# stm32uni.net
KiCad netlist of a schematic drawn in EAGLE
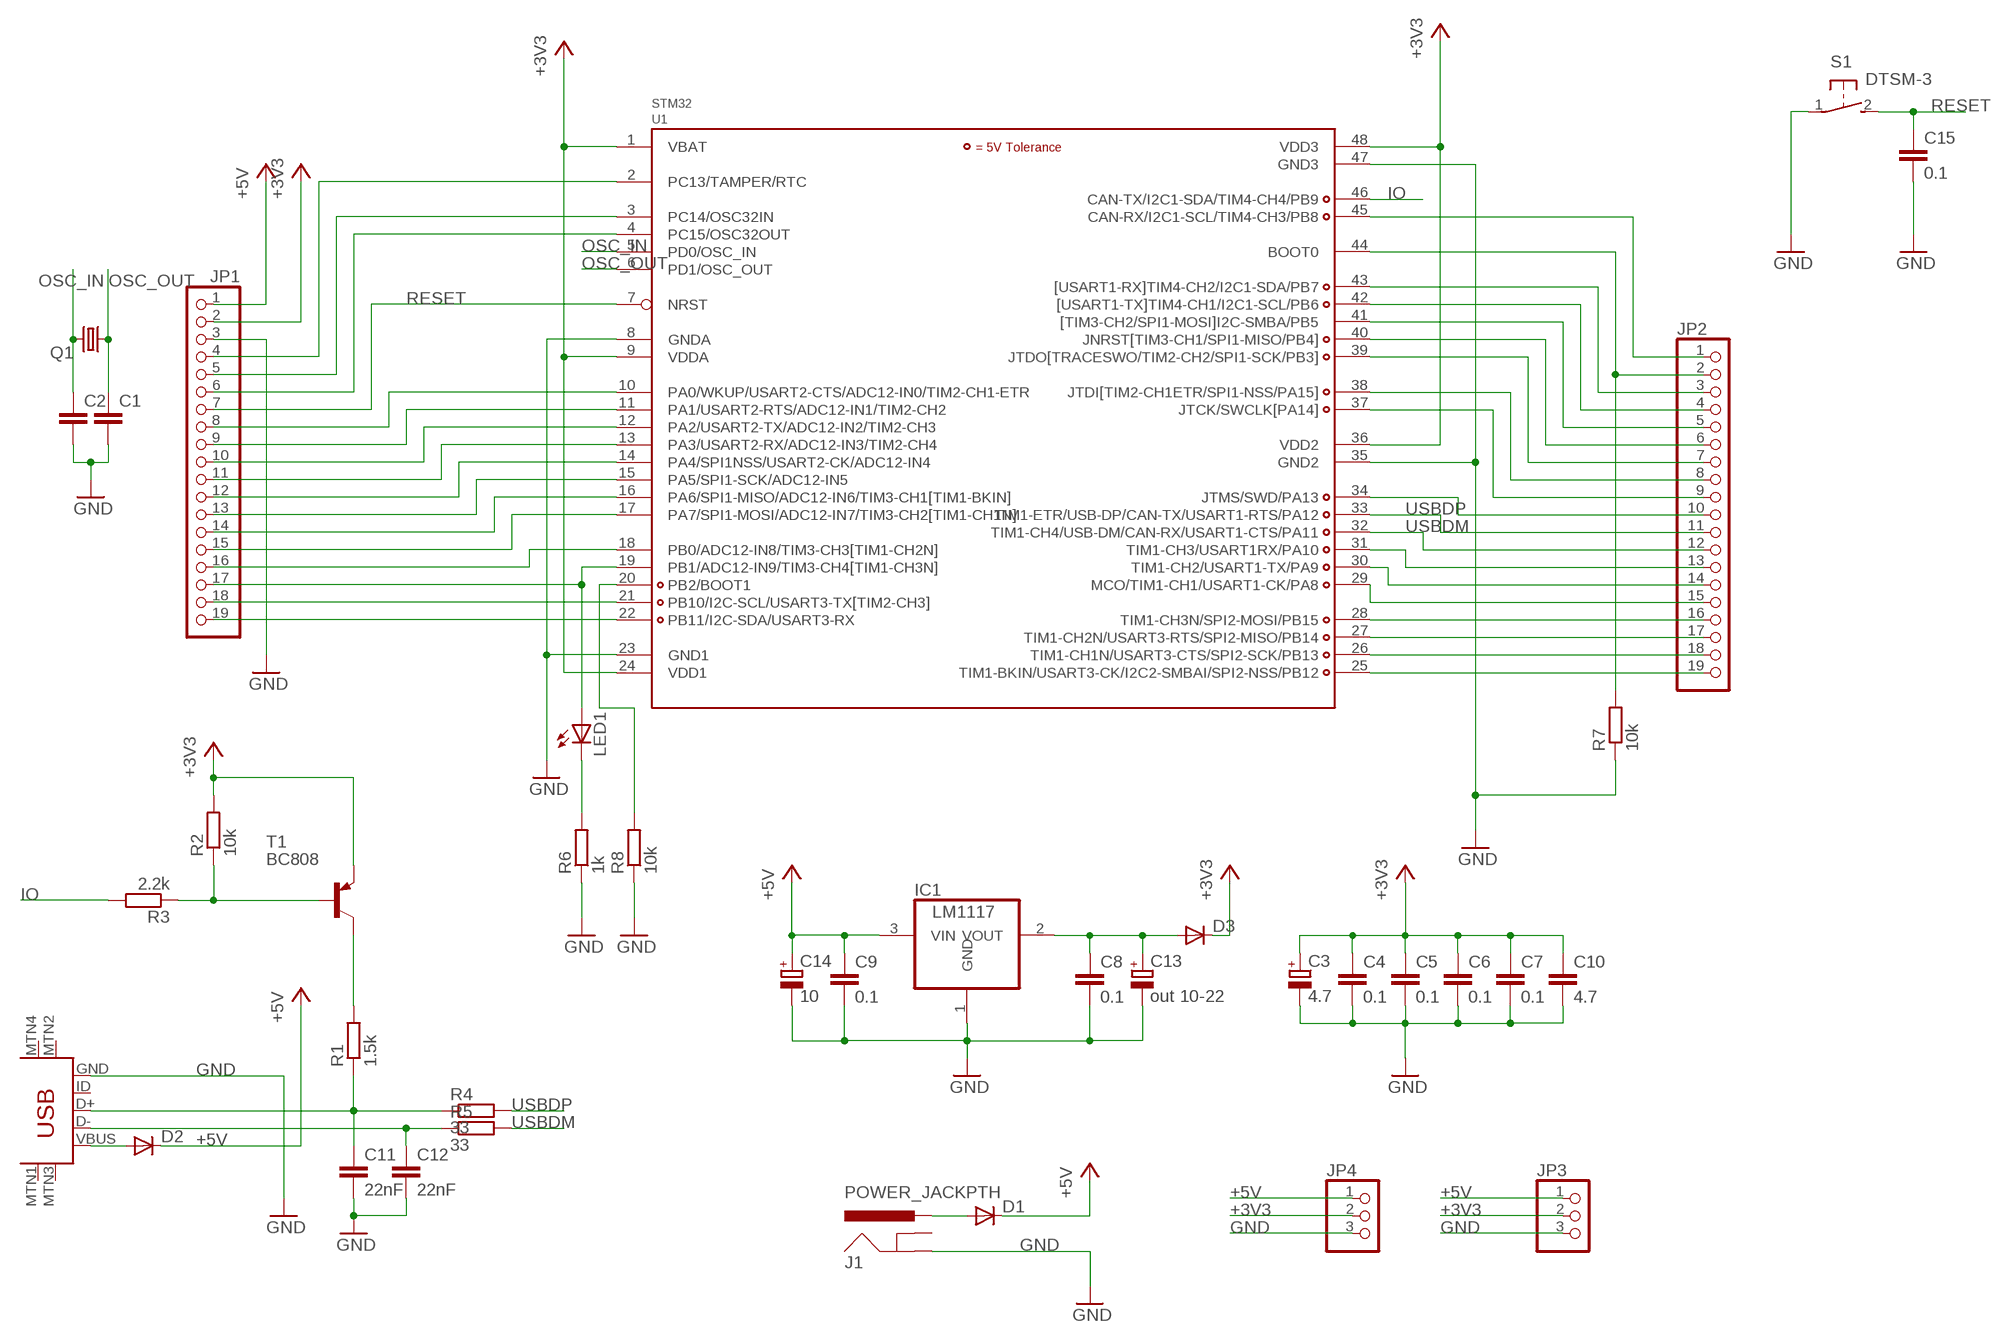
[diagram p0: schematic, sheet 1]

(export (version "E")
  (design (tool "Eeschema 10.0.6"))
  (components
    (comp (ref "C1")
      (value "C-EUC0805")
      (footprint "eagle-import:C0805")
      (libsource (lib "eagle-import") (part "C-EUC0805"))
    )
    (comp (ref "C2")
      (value "C-EUC0805")
      (footprint "eagle-import:C0805")
      (libsource (lib "eagle-import") (part "C-EUC0805"))
    )
    (comp (ref "C3")
      (value "4.7")
      (footprint "eagle-import:SMC_B")
      (libsource (lib "eagle-import") (part "CPOL-EUSMCB"))
    )
    (comp (ref "C4")
      (value "0.1")
      (footprint "eagle-import:C0805")
      (libsource (lib "eagle-import") (part "C-EUC0805"))
    )
    (comp (ref "C5")
      (value "0.1")
      (footprint "eagle-import:C0805")
      (libsource (lib "eagle-import") (part "C-EUC0805"))
    )
    (comp (ref "C6")
      (value "0.1")
      (footprint "eagle-import:C0805")
      (libsource (lib "eagle-import") (part "C-EUC0805"))
    )
    (comp (ref "C7")
      (value "0.1")
      (footprint "eagle-import:C0805")
      (libsource (lib "eagle-import") (part "C-EUC0805"))
    )
    (comp (ref "C8")
      (value "0.1")
      (footprint "eagle-import:C0805")
      (libsource (lib "eagle-import") (part "C-EUC0805"))
    )
    (comp (ref "C9")
      (value "0.1")
      (footprint "eagle-import:C0805")
      (libsource (lib "eagle-import") (part "C-EUC0805"))
    )
    (comp (ref "C10")
      (value "4.7")
      (footprint "eagle-import:C0805")
      (libsource (lib "eagle-import") (part "C-EUC0805"))
    )
    (comp (ref "C11")
      (value "22nF")
      (footprint "eagle-import:C0805")
      (libsource (lib "eagle-import") (part "C-EUC0805"))
    )
    (comp (ref "C12")
      (value "22nF")
      (footprint "eagle-import:C0805")
      (libsource (lib "eagle-import") (part "C-EUC0805"))
    )
    (comp (ref "C13")
      (value "out 10-22")
      (footprint "eagle-import:SMC_B")
      (libsource (lib "eagle-import") (part "CPOL-EUSMCB"))
    )
    (comp (ref "C14")
      (value "10")
      (footprint "eagle-import:SMC_B")
      (libsource (lib "eagle-import") (part "CPOL-EUSMCB"))
    )
    (comp (ref "C15")
      (value "0.1")
      (footprint "eagle-import:C0805")
      (libsource (lib "eagle-import") (part "C-EUC0805"))
    )
    (comp (ref "D1")
      (value "DIODE-SOD123")
      (footprint "eagle-import:SOD123")
      (libsource (lib "eagle-import") (part "DIODE-SOD123"))
    )
    (comp (ref "D2")
      (value "DIODE-SOD123")
      (footprint "eagle-import:SOD123")
      (libsource (lib "eagle-import") (part "DIODE-SOD123"))
    )
    (comp (ref "D3")
      (value "DIODE-SOD123")
      (footprint "eagle-import:SOD123")
      (libsource (lib "eagle-import") (part "DIODE-SOD123"))
    )
    (comp (ref "IC1")
      (value "LM1117")
      (footprint "eagle-import:SOT223")
      (fields (field (name "MPN") "REG1117"))
      (libsource (lib "eagle-import") (part "REG1117"))
    )
    (comp (ref "J1")
      (value "POWER_JACKPTH")
      (footprint "eagle-import:POWER_JACK_PTH")
      (libsource (lib "eagle-import") (part "POWER_JACKPTH"))
    )
    (comp (ref "JP1")
      (value "PINHD-1X19")
      (footprint "eagle-import:1X19")
      (libsource (lib "eagle-import") (part "PINHD-1X19"))
    )
    (comp (ref "JP2")
      (value "PINHD-1X19")
      (footprint "eagle-import:1X19")
      (libsource (lib "eagle-import") (part "PINHD-1X19"))
    )
    (comp (ref "JP3")
      (value "PINHD-1X3")
      (footprint "eagle-import:1X03")
      (libsource (lib "eagle-import") (part "PINHD-1X3"))
    )
    (comp (ref "JP4")
      (value "PINHD-1X3")
      (footprint "eagle-import:1X03")
      (libsource (lib "eagle-import") (part "PINHD-1X3"))
    )
    (comp (ref "LED1")
      (value "LEDCHIPLED_0805")
      (footprint "eagle-import:CHIPLED_0805")
      (libsource (lib "eagle-import") (part "LEDCHIPLED_0805"))
    )
    (comp (ref "Q1")
      (value "CRYSTALHC49UP")
      (footprint "eagle-import:HC49UP")
      (libsource (lib "eagle-import") (part "CRYSTALHC49UP"))
    )
    (comp (ref "R1")
      (value "1.5k")
      (footprint "eagle-import:R0805")
      (libsource (lib "eagle-import") (part "R-EU_R0805"))
    )
    (comp (ref "R2")
      (value "10k")
      (footprint "eagle-import:R0805")
      (libsource (lib "eagle-import") (part "R-EU_R0805"))
    )
    (comp (ref "R3")
      (value "2.2k")
      (footprint "eagle-import:R0805")
      (libsource (lib "eagle-import") (part "R-EU_R0805"))
    )
    (comp (ref "R4")
      (value "33")
      (footprint "eagle-import:R0805")
      (libsource (lib "eagle-import") (part "R-EU_R0805"))
    )
    (comp (ref "R5")
      (value "33")
      (footprint "eagle-import:R0805")
      (libsource (lib "eagle-import") (part "R-EU_R0805"))
    )
    (comp (ref "R6")
      (value "1k")
      (footprint "eagle-import:R0805")
      (libsource (lib "eagle-import") (part "R-EU_R0805"))
    )
    (comp (ref "R7")
      (value "10k")
      (footprint "eagle-import:R0805")
      (libsource (lib "eagle-import") (part "R-EU_R0805"))
    )
    (comp (ref "R8")
      (value "10k")
      (footprint "eagle-import:R0805")
      (libsource (lib "eagle-import") (part "R-EU_R0805"))
    )
    (comp (ref "S1")
      (value "DTSM-3")
      (footprint "eagle-import:DTSM-3")
      (libsource (lib "eagle-import") (part "DTSM-3"))
    )
    (comp (ref "T1")
      (value "BC808")
      (footprint "eagle-import:SOT23-BEC")
      (libsource (lib "eagle-import") (part "-PNP-SOT23-BECBC808-16"))
    )
    (comp (ref "U$1")
      (value "USB-MINIB-5PIN")
      (footprint "eagle-import:USB-MINIB")
      (libsource (lib "eagle-import") (part "USB-MINIB-5PIN"))
    )
    (comp (ref "U1")
      (value "STM32")
      (footprint "eagle-import:LQFP48")
      (libsource (lib "eagle-import") (part "STM32F103C8LQFP48"))
    )
  )
  (nets
    (net (code "1") (name "+3V3") (class "Default")
      (node (ref "C10") (pin "1") (pinfunction "1_1") (pintype "passive"))
      (node (ref "C3") (pin "+") (pinfunction "+_+") (pintype "passive"))
      (node (ref "C4") (pin "1") (pinfunction "1_1") (pintype "passive"))
      (node (ref "C5") (pin "1") (pinfunction "1_1") (pintype "passive"))
      (node (ref "C6") (pin "1") (pinfunction "1_1") (pintype "passive"))
      (node (ref "C7") (pin "1") (pinfunction "1_1") (pintype "passive"))
      (node (ref "D3") (pin "C") (pinfunction "C_C") (pintype "passive"))
      (node (ref "JP1") (pin "2") (pinfunction "2_2") (pintype "passive"))
      (node (ref "JP3") (pin "2") (pinfunction "2_2") (pintype "passive"))
      (node (ref "JP4") (pin "2") (pinfunction "2_2") (pintype "passive"))
      (node (ref "R2") (pin "2") (pinfunction "2_2") (pintype "passive"))
      (node (ref "T1") (pin "E") (pinfunction "E_E") (pintype "passive"))
      (node (ref "U1") (pin "1") (pinfunction "VBAT_1") (pintype "power_in"))
      (node (ref "U1") (pin "24") (pinfunction "VDD1_24") (pintype "power_in"))
      (node (ref "U1") (pin "36") (pinfunction "VDD2_36") (pintype "power_in"))
      (node (ref "U1") (pin "48") (pinfunction "VDD3_48") (pintype "power_in"))
      (node (ref "U1") (pin "9") (pinfunction "VDDA_9") (pintype "power_in"))
    )
    (net (code "2") (name "+5V") (class "Default")
      (node (ref "C14") (pin "+") (pinfunction "+_+") (pintype "passive"))
      (node (ref "C9") (pin "1") (pinfunction "1_1") (pintype "passive"))
      (node (ref "D1") (pin "C") (pinfunction "C_C") (pintype "passive"))
      (node (ref "D2") (pin "C") (pinfunction "C_C") (pintype "passive"))
      (node (ref "IC1") (pin "3") (pinfunction "VIN_3") (pintype "input"))
      (node (ref "JP1") (pin "1") (pinfunction "1_1") (pintype "passive"))
      (node (ref "JP3") (pin "1") (pinfunction "1_1") (pintype "passive"))
      (node (ref "JP4") (pin "1") (pinfunction "1_1") (pintype "passive"))
    )
    (net (code "3") (name "/IO") (class "Default")
      (node (ref "R3") (pin "2") (pinfunction "2_2") (pintype "passive"))
      (node (ref "U1") (pin "46") (pinfunction "CAN-TX/I2C1-SDA/TIM4-CH4/PB9_46") (pintype "bidirectional"))
    )
    (net (code "4") (name "/OSC_IN") (class "Default")
      (node (ref "C2") (pin "1") (pinfunction "1_1") (pintype "passive"))
      (node (ref "Q1") (pin "2") (pinfunction "2_2") (pintype "passive"))
      (node (ref "U1") (pin "5") (pinfunction "PD0/OSC_IN_5") (pintype "bidirectional"))
    )
    (net (code "5") (name "/OSC_OUT") (class "Default")
      (node (ref "C1") (pin "1") (pinfunction "1_1") (pintype "passive"))
      (node (ref "Q1") (pin "1") (pinfunction "1_1") (pintype "passive"))
      (node (ref "U1") (pin "6") (pinfunction "PD1/OSC_OUT_6") (pintype "bidirectional"))
    )
    (net (code "6") (name "/RESET") (class "Default")
      (node (ref "C15") (pin "1") (pinfunction "1_1") (pintype "passive"))
      (node (ref "JP1") (pin "7") (pinfunction "7_7") (pintype "passive"))
      (node (ref "S1") (pin "2") (pinfunction "2_2") (pintype "passive"))
      (node (ref "U1") (pin "7") (pinfunction "NRST_7") (pintype "bidirectional"))
    )
    (net (code "7") (name "/USBDM") (class "Default")
      (node (ref "JP2") (pin "12") (pinfunction "12_12") (pintype "passive"))
      (node (ref "R5") (pin "2") (pinfunction "2_2") (pintype "passive"))
      (node (ref "U1") (pin "32") (pinfunction "TIM1-CH4/USB-DM/CAN-RX/USART1-CTS/PA11_32") (pintype "bidirectional"))
    )
    (net (code "8") (name "/USBDP") (class "Default")
      (node (ref "JP2") (pin "11") (pinfunction "11_11") (pintype "passive"))
      (node (ref "R4") (pin "2") (pinfunction "2_2") (pintype "passive"))
      (node (ref "U1") (pin "33") (pinfunction "TIM1-ETR/USB-DP/CAN-TX/USART1-RTS/PA12_33") (pintype "bidirectional"))
    )
    (net (code "9") (name "GND") (class "Default")
      (node (ref "C1") (pin "2") (pinfunction "2_2") (pintype "passive"))
      (node (ref "C10") (pin "2") (pinfunction "2_2") (pintype "passive"))
      (node (ref "C11") (pin "2") (pinfunction "2_2") (pintype "passive"))
      (node (ref "C12") (pin "2") (pinfunction "2_2") (pintype "passive"))
      (node (ref "C13") (pin "-") (pinfunction "-_-") (pintype "passive"))
      (node (ref "C14") (pin "-") (pinfunction "-_-") (pintype "passive"))
      (node (ref "C15") (pin "2") (pinfunction "2_2") (pintype "passive"))
      (node (ref "C2") (pin "2") (pinfunction "2_2") (pintype "passive"))
      (node (ref "C3") (pin "-") (pinfunction "-_-") (pintype "passive"))
      (node (ref "C4") (pin "2") (pinfunction "2_2") (pintype "passive"))
      (node (ref "C5") (pin "2") (pinfunction "2_2") (pintype "passive"))
      (node (ref "C6") (pin "2") (pinfunction "2_2") (pintype "passive"))
      (node (ref "C7") (pin "2") (pinfunction "2_2") (pintype "passive"))
      (node (ref "C8") (pin "2") (pinfunction "2_2") (pintype "passive"))
      (node (ref "C9") (pin "2") (pinfunction "2_2") (pintype "passive"))
      (node (ref "IC1") (pin "1") (pinfunction "GND_1") (pintype "power_in"))
      (node (ref "J1") (pin "GND") (pinfunction "GND_GND") (pintype "bidirectional"))
      (node (ref "JP1") (pin "3") (pinfunction "3_3") (pintype "passive"))
      (node (ref "JP3") (pin "3") (pinfunction "3_3") (pintype "passive"))
      (node (ref "JP4") (pin "3") (pinfunction "3_3") (pintype "passive"))
      (node (ref "R6") (pin "1") (pinfunction "1_1") (pintype "passive"))
      (node (ref "R7") (pin "1") (pinfunction "1_1") (pintype "passive"))
      (node (ref "R8") (pin "1") (pinfunction "1_1") (pintype "passive"))
      (node (ref "S1") (pin "1") (pinfunction "1_1") (pintype "passive"))
      (node (ref "U$1") (pin "GND") (pinfunction "GND_GND") (pintype "bidirectional"))
      (node (ref "U1") (pin "23") (pinfunction "GND1_23") (pintype "power_in"))
      (node (ref "U1") (pin "35") (pinfunction "GND2_35") (pintype "power_in"))
      (node (ref "U1") (pin "47") (pinfunction "GND3_47") (pintype "power_in"))
      (node (ref "U1") (pin "8") (pinfunction "GNDA_8") (pintype "power_in"))
    )
    (net (code "10") (name "Net-(C11-Pad1)") (class "Default")
      (node (ref "C11") (pin "1") (pinfunction "1_1") (pintype "passive"))
      (node (ref "R1") (pin "1") (pinfunction "1_1") (pintype "passive"))
      (node (ref "R4") (pin "1") (pinfunction "1_1") (pintype "passive"))
      (node (ref "U$1") (pin "D+") (pinfunction "D+_D+") (pintype "bidirectional"))
    )
    (net (code "11") (name "Net-(C12-Pad1)") (class "Default")
      (node (ref "C12") (pin "1") (pinfunction "1_1") (pintype "passive"))
      (node (ref "R5") (pin "1") (pinfunction "1_1") (pintype "passive"))
      (node (ref "U$1") (pin "D-") (pinfunction "D-_D-") (pintype "bidirectional"))
    )
    (net (code "12") (name "Net-(D1-PadA)") (class "Default")
      (node (ref "D1") (pin "A") (pinfunction "A_A") (pintype "passive"))
      (node (ref "J1") (pin "PWR") (pinfunction "PWR_PWR") (pintype "bidirectional"))
    )
    (net (code "13") (name "Net-(D2-PadA)") (class "Default")
      (node (ref "D2") (pin "A") (pinfunction "A_A") (pintype "passive"))
      (node (ref "U$1") (pin "VBUS") (pinfunction "VBUS_VBUS") (pintype "bidirectional"))
    )
    (net (code "14") (name "Net-(IC1-VOUT)") (class "Default")
      (node (ref "C13") (pin "+") (pinfunction "+_+") (pintype "passive"))
      (node (ref "C8") (pin "1") (pinfunction "1_1") (pintype "passive"))
      (node (ref "D3") (pin "A") (pinfunction "A_A") (pintype "passive"))
      (node (ref "IC1") (pin "2") (pinfunction "VOUT_2") (pintype "output"))
    )
    (net (code "15") (name "Net-(LED1-PadC)") (class "Default")
      (node (ref "LED1") (pin "C") (pinfunction "C_C") (pintype "passive"))
      (node (ref "R6") (pin "2") (pinfunction "2_2") (pintype "passive"))
    )
    (net (code "16") (name "Net-(R1-Pad2)") (class "Default")
      (node (ref "R1") (pin "2") (pinfunction "2_2") (pintype "passive"))
      (node (ref "T1") (pin "C") (pinfunction "C_C") (pintype "passive"))
    )
    (net (code "17") (name "Net-(R2-Pad1)") (class "Default")
      (node (ref "R2") (pin "1") (pinfunction "1_1") (pintype "passive"))
      (node (ref "R3") (pin "1") (pinfunction "1_1") (pintype "passive"))
      (node (ref "T1") (pin "B") (pinfunction "B_B") (pintype "passive"))
    )
    (net (code "18") (name "Net-(U1-BOOT0)") (class "Default")
      (node (ref "JP2") (pin "2") (pinfunction "2_2") (pintype "passive"))
      (node (ref "R7") (pin "2") (pinfunction "2_2") (pintype "passive"))
      (node (ref "U1") (pin "44") (pinfunction "BOOT0_44") (pintype "bidirectional"))
    )
    (net (code "19") (name "Net-(U1-CAN-RX{slash}I2C1-SCL{slash}TIM4-CH3{slash}PB8)") (class "Default")
      (node (ref "JP2") (pin "1") (pinfunction "1_1") (pintype "passive"))
      (node (ref "U1") (pin "45") (pinfunction "CAN-RX/I2C1-SCL/TIM4-CH3/PB8_45") (pintype "bidirectional"))
    )
    (net (code "20") (name "Net-(U1-JNRST[TIM3-CH1{slash}SPI1-MISO{slash}PB4])") (class "Default")
      (node (ref "JP2") (pin "6") (pinfunction "6_6") (pintype "passive"))
      (node (ref "U1") (pin "40") (pinfunction "JNRST[TIM3-CH1/SPI1-MISO/PB4]_40") (pintype "bidirectional"))
    )
    (net (code "21") (name "Net-(U1-JTCK{slash}SWCLK[PA14])") (class "Default")
      (node (ref "JP2") (pin "9") (pinfunction "9_9") (pintype "passive"))
      (node (ref "U1") (pin "37") (pinfunction "JTCK/SWCLK[PA14]_37") (pintype "bidirectional"))
    )
    (net (code "22") (name "Net-(U1-JTDI[TIM2-CH1ETR{slash}SPI1-NSS{slash}PA15])") (class "Default")
      (node (ref "JP2") (pin "8") (pinfunction "8_8") (pintype "passive"))
      (node (ref "U1") (pin "38") (pinfunction "JTDI[TIM2-CH1ETR/SPI1-NSS/PA15]_38") (pintype "bidirectional"))
    )
    (net (code "23") (name "Net-(U1-JTDO[TRACESWO{slash}TIM2-CH2{slash}SPI1-SCK{slash}PB3])") (class "Default")
      (node (ref "JP2") (pin "7") (pinfunction "7_7") (pintype "passive"))
      (node (ref "U1") (pin "39") (pinfunction "JTDO[TRACESWO/TIM2-CH2/SPI1-SCK/PB3]_39") (pintype "bidirectional"))
    )
    (net (code "24") (name "Net-(U1-JTMS{slash}SWD{slash}PA13)") (class "Default")
      (node (ref "JP2") (pin "10") (pinfunction "10_10") (pintype "passive"))
      (node (ref "U1") (pin "34") (pinfunction "JTMS/SWD/PA13_34") (pintype "bidirectional"))
    )
    (net (code "25") (name "Net-(U1-MCO{slash}TIM1-CH1{slash}USART1-CK{slash}PA8)") (class "Default")
      (node (ref "JP2") (pin "15") (pinfunction "15_15") (pintype "passive"))
      (node (ref "U1") (pin "29") (pinfunction "MCO/TIM1-CH1/USART1-CK/PA8_29") (pintype "bidirectional"))
    )
    (net (code "26") (name "Net-(U1-PA0{slash}WKUP{slash}USART2-CTS{slash}ADC12-IN0{slash}TIM2-CH1-ETR)") (class "Default")
      (node (ref "JP1") (pin "8") (pinfunction "8_8") (pintype "passive"))
      (node (ref "U1") (pin "10") (pinfunction "PA0/WKUP/USART2-CTS/ADC12-IN0/TIM2-CH1-ETR_10") (pintype "bidirectional"))
    )
    (net (code "27") (name "Net-(U1-PA1{slash}USART2-RTS{slash}ADC12-IN1{slash}TIM2-CH2)") (class "Default")
      (node (ref "JP1") (pin "9") (pinfunction "9_9") (pintype "passive"))
      (node (ref "U1") (pin "11") (pinfunction "PA1/USART2-RTS/ADC12-IN1/TIM2-CH2_11") (pintype "bidirectional"))
    )
    (net (code "28") (name "Net-(U1-PA2{slash}USART2-TX{slash}ADC12-IN2{slash}TIM2-CH3)") (class "Default")
      (node (ref "JP1") (pin "10") (pinfunction "10_10") (pintype "passive"))
      (node (ref "U1") (pin "12") (pinfunction "PA2/USART2-TX/ADC12-IN2/TIM2-CH3_12") (pintype "bidirectional"))
    )
    (net (code "29") (name "Net-(U1-PA3{slash}USART2-RX{slash}ADC12-IN3{slash}TIM2-CH4)") (class "Default")
      (node (ref "JP1") (pin "11") (pinfunction "11_11") (pintype "passive"))
      (node (ref "U1") (pin "13") (pinfunction "PA3/USART2-RX/ADC12-IN3/TIM2-CH4_13") (pintype "bidirectional"))
    )
    (net (code "30") (name "Net-(U1-PA4{slash}SPI1NSS{slash}USART2-CK{slash}ADC12-IN4)") (class "Default")
      (node (ref "JP1") (pin "12") (pinfunction "12_12") (pintype "passive"))
      (node (ref "U1") (pin "14") (pinfunction "PA4/SPI1NSS/USART2-CK/ADC12-IN4_14") (pintype "bidirectional"))
    )
    (net (code "31") (name "Net-(U1-PA5{slash}SPI1-SCK{slash}ADC12-IN5)") (class "Default")
      (node (ref "JP1") (pin "13") (pinfunction "13_13") (pintype "passive"))
      (node (ref "U1") (pin "15") (pinfunction "PA5/SPI1-SCK/ADC12-IN5_15") (pintype "bidirectional"))
    )
    (net (code "32") (name "Net-(U1-PA6{slash}SPI1-MISO{slash}ADC12-IN6{slash}TIM3-CH1[TIM1-BKIN])") (class "Default")
      (node (ref "JP1") (pin "14") (pinfunction "14_14") (pintype "passive"))
      (node (ref "U1") (pin "16") (pinfunction "PA6/SPI1-MISO/ADC12-IN6/TIM3-CH1[TIM1-BKIN]_16") (pintype "bidirectional"))
    )
    (net (code "33") (name "Net-(U1-PA7{slash}SPI1-MOSI{slash}ADC12-IN7{slash}TIM3-CH2[TIM1-CH1N])") (class "Default")
      (node (ref "JP1") (pin "15") (pinfunction "15_15") (pintype "passive"))
      (node (ref "U1") (pin "17") (pinfunction "PA7/SPI1-MOSI/ADC12-IN7/TIM3-CH2[TIM1-CH1N]_17") (pintype "bidirectional"))
    )
    (net (code "34") (name "Net-(U1-PB0{slash}ADC12-IN8{slash}TIM3-CH3[TIM1-CH2N])") (class "Default")
      (node (ref "JP1") (pin "16") (pinfunction "16_16") (pintype "passive"))
      (node (ref "U1") (pin "18") (pinfunction "PB0/ADC12-IN8/TIM3-CH3[TIM1-CH2N]_18") (pintype "bidirectional"))
    )
    (net (code "35") (name "Net-(U1-PB1{slash}ADC12-IN9{slash}TIM3-CH4[TIM1-CH3N])") (class "Default")
      (node (ref "JP1") (pin "17") (pinfunction "17_17") (pintype "passive"))
      (node (ref "LED1") (pin "A") (pinfunction "A_A") (pintype "passive"))
      (node (ref "U1") (pin "19") (pinfunction "PB1/ADC12-IN9/TIM3-CH4[TIM1-CH3N]_19") (pintype "bidirectional"))
    )
    (net (code "36") (name "Net-(U1-PB2{slash}BOOT1)") (class "Default")
      (node (ref "R8") (pin "2") (pinfunction "2_2") (pintype "passive"))
      (node (ref "U1") (pin "20") (pinfunction "PB2/BOOT1_20") (pintype "bidirectional"))
    )
    (net (code "37") (name "Net-(U1-PB10{slash}I2C-SCL{slash}USART3-TX[TIM2-CH3])") (class "Default")
      (node (ref "JP1") (pin "18") (pinfunction "18_18") (pintype "passive"))
      (node (ref "U1") (pin "21") (pinfunction "PB10/I2C-SCL/USART3-TX[TIM2-CH3]_21") (pintype "bidirectional"))
    )
    (net (code "38") (name "Net-(U1-PB11{slash}I2C-SDA{slash}USART3-RX)") (class "Default")
      (node (ref "JP1") (pin "19") (pinfunction "19_19") (pintype "passive"))
      (node (ref "U1") (pin "22") (pinfunction "PB11/I2C-SDA/USART3-RX_22") (pintype "bidirectional"))
    )
    (net (code "39") (name "Net-(U1-PC13{slash}TAMPER{slash}RTC)") (class "Default")
      (node (ref "JP1") (pin "4") (pinfunction "4_4") (pintype "passive"))
      (node (ref "U1") (pin "2") (pinfunction "PC13/TAMPER/RTC_2") (pintype "bidirectional"))
    )
    (net (code "40") (name "Net-(U1-PC14{slash}OSC32IN)") (class "Default")
      (node (ref "JP1") (pin "5") (pinfunction "5_5") (pintype "passive"))
      (node (ref "U1") (pin "3") (pinfunction "PC14/OSC32IN_3") (pintype "bidirectional"))
    )
    (net (code "41") (name "Net-(U1-PC15{slash}OSC32OUT)") (class "Default")
      (node (ref "JP1") (pin "6") (pinfunction "6_6") (pintype "passive"))
      (node (ref "U1") (pin "4") (pinfunction "PC15/OSC32OUT_4") (pintype "bidirectional"))
    )
    (net (code "42") (name "Net-(U1-TIM1-BKIN{slash}USART3-CK{slash}I2C2-SMBAI{slash}SPI2-NSS{slash}PB12)") (class "Default")
      (node (ref "JP2") (pin "19") (pinfunction "19_19") (pintype "passive"))
      (node (ref "U1") (pin "25") (pinfunction "TIM1-BKIN/USART3-CK/I2C2-SMBAI/SPI2-NSS/PB12_25") (pintype "bidirectional"))
    )
    (net (code "43") (name "Net-(U1-TIM1-CH1N{slash}USART3-CTS{slash}SPI2-SCK{slash}PB13)") (class "Default")
      (node (ref "JP2") (pin "18") (pinfunction "18_18") (pintype "passive"))
      (node (ref "U1") (pin "26") (pinfunction "TIM1-CH1N/USART3-CTS/SPI2-SCK/PB13_26") (pintype "bidirectional"))
    )
    (net (code "44") (name "Net-(U1-TIM1-CH2N{slash}USART3-RTS{slash}SPI2-MISO{slash}PB14)") (class "Default")
      (node (ref "JP2") (pin "17") (pinfunction "17_17") (pintype "passive"))
      (node (ref "U1") (pin "27") (pinfunction "TIM1-CH2N/USART3-RTS/SPI2-MISO/PB14_27") (pintype "bidirectional"))
    )
    (net (code "45") (name "Net-(U1-TIM1-CH2{slash}USART1-TX{slash}PA9)") (class "Default")
      (node (ref "JP2") (pin "14") (pinfunction "14_14") (pintype "passive"))
      (node (ref "U1") (pin "30") (pinfunction "TIM1-CH2/USART1-TX/PA9_30") (pintype "bidirectional"))
    )
    (net (code "46") (name "Net-(U1-TIM1-CH3N{slash}SPI2-MOSI{slash}PB15)") (class "Default")
      (node (ref "JP2") (pin "16") (pinfunction "16_16") (pintype "passive"))
      (node (ref "U1") (pin "28") (pinfunction "TIM1-CH3N/SPI2-MOSI/PB15_28") (pintype "bidirectional"))
    )
    (net (code "47") (name "Net-(U1-TIM1-CH3{slash}USART1RX{slash}PA10)") (class "Default")
      (node (ref "JP2") (pin "13") (pinfunction "13_13") (pintype "passive"))
      (node (ref "U1") (pin "31") (pinfunction "TIM1-CH3/USART1RX/PA10_31") (pintype "bidirectional"))
    )
    (net (code "48") (name "Net-(U1-[TIM3-CH2{slash}SPI1-MOSI]I2C-SMBA{slash}PB5)") (class "Default")
      (node (ref "JP2") (pin "5") (pinfunction "5_5") (pintype "passive"))
      (node (ref "U1") (pin "41") (pinfunction "[TIM3-CH2/SPI1-MOSI]I2C-SMBA/PB5_41") (pintype "bidirectional"))
    )
    (net (code "49") (name "Net-(U1-[USART1-RX]TIM4-CH2{slash}I2C1-SDA{slash}PB7)") (class "Default")
      (node (ref "JP2") (pin "3") (pinfunction "3_3") (pintype "passive"))
      (node (ref "U1") (pin "43") (pinfunction "[USART1-RX]TIM4-CH2/I2C1-SDA/PB7_43") (pintype "bidirectional"))
    )
    (net (code "50") (name "Net-(U1-[USART1-TX]TIM4-CH1{slash}I2C1-SCL{slash}PB6)") (class "Default")
      (node (ref "JP2") (pin "4") (pinfunction "4_4") (pintype "passive"))
      (node (ref "U1") (pin "42") (pinfunction "[USART1-TX]TIM4-CH1/I2C1-SCL/PB6_42") (pintype "bidirectional"))
    )
    (net (code "51") (name "unconnected-(J1-PadGNDBREAK)") (class "Default")
      (node (ref "J1") (pin "GNDBREAK") (pinfunction "GNDBREAK_GNDBREAK") (pintype "bidirectional"))
    )
    (net (code "52") (name "unconnected-(U$1-MTN1-PadMTN3)") (class "Default")
      (node (ref "U$1") (pin "MTN3") (pinfunction "MTN1_MTN3") (pintype "bidirectional"))
    )
    (net (code "53") (name "unconnected-(U$1-MTN2-PadMTN1)") (class "Default")
      (node (ref "U$1") (pin "MTN1") (pinfunction "MTN2_MTN1") (pintype "bidirectional"))
    )
    (net (code "54") (name "unconnected-(U$1-MTN3-PadMTN2)") (class "Default")
      (node (ref "U$1") (pin "MTN2") (pinfunction "MTN3_MTN2") (pintype "bidirectional"))
    )
    (net (code "55") (name "unconnected-(U$1-PadID)") (class "Default")
      (node (ref "U$1") (pin "ID") (pinfunction "ID_ID") (pintype "bidirectional"))
    )
    (net (code "56") (name "unconnected-(U$1-PadMTN4)") (class "Default")
      (node (ref "U$1") (pin "MTN4") (pinfunction "MTN4_MTN4") (pintype "bidirectional"))
    )
  )
)
